# DCCInterfaceShieldNano.net
KiCad netlist of a schematic drawn in EAGLE
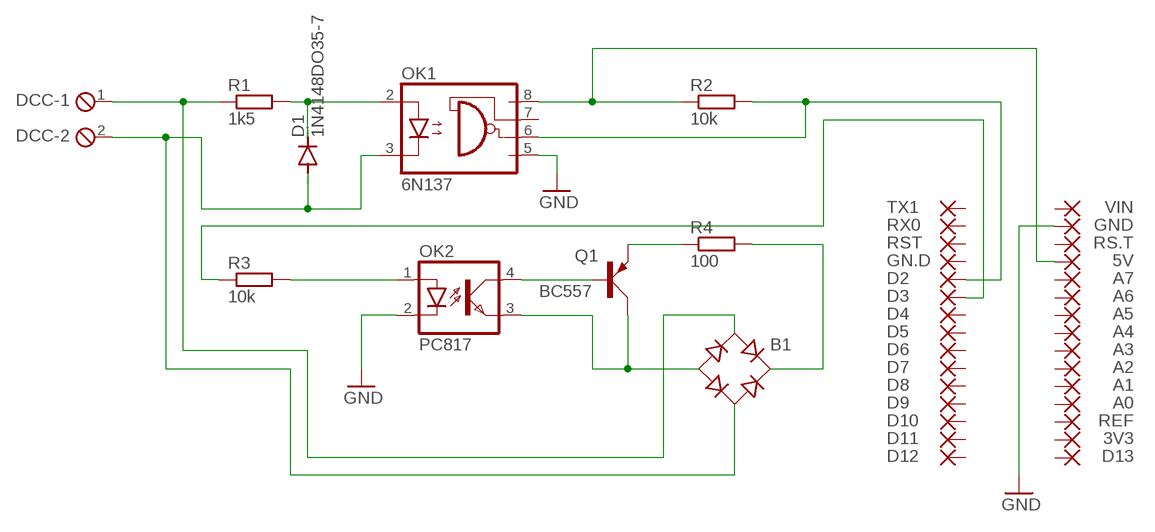
[diagram p0: schematic, sheet 1]

(export (version "E")
  (design (tool "Eeschema 10.0.6"))
  (components
    (comp (ref "3V3")
      (value "1,6/0,8")
      (footprint "eagle-import:1,6_0,8")
      (libsource (lib "eagle-import") (part "1,6/0,8"))
    )
    (comp (ref "5V")
      (value "1,6/0,8")
      (footprint "eagle-import:1,6_0,8")
      (libsource (lib "eagle-import") (part "1,6/0,8"))
    )
    (comp (ref "A0")
      (value "1,6/0,8")
      (footprint "eagle-import:1,6_0,8")
      (libsource (lib "eagle-import") (part "1,6/0,8"))
    )
    (comp (ref "A1")
      (value "1,6/0,8")
      (footprint "eagle-import:1,6_0,8")
      (libsource (lib "eagle-import") (part "1,6/0,8"))
    )
    (comp (ref "A2")
      (value "1,6/0,8")
      (footprint "eagle-import:1,6_0,8")
      (libsource (lib "eagle-import") (part "1,6/0,8"))
    )
    (comp (ref "A3")
      (value "1,6/0,8")
      (footprint "eagle-import:1,6_0,8")
      (libsource (lib "eagle-import") (part "1,6/0,8"))
    )
    (comp (ref "A4")
      (value "1,6/0,8")
      (footprint "eagle-import:1,6_0,8")
      (libsource (lib "eagle-import") (part "1,6/0,8"))
    )
    (comp (ref "A5")
      (value "1,6/0,8")
      (footprint "eagle-import:1,6_0,8")
      (libsource (lib "eagle-import") (part "1,6/0,8"))
    )
    (comp (ref "A6")
      (value "1,6/0,8")
      (footprint "eagle-import:1,6_0,8")
      (libsource (lib "eagle-import") (part "1,6/0,8"))
    )
    (comp (ref "A7")
      (value "1,6/0,8")
      (footprint "eagle-import:1,6_0,8")
      (libsource (lib "eagle-import") (part "1,6/0,8"))
    )
    (comp (ref "B1")
      (value "RB1A")
      (footprint "eagle-import:RB1A")
      (libsource (lib "eagle-import") (part "RB1A"))
    )
    (comp (ref "D1")
      (value "1N4148DO35-7")
      (footprint "eagle-import:DO35-7")
      (libsource (lib "eagle-import") (part "1N4148DO35-7"))
    )
    (comp (ref "D2")
      (value "1,6/0,8")
      (footprint "eagle-import:1,6_0,8")
      (libsource (lib "eagle-import") (part "1,6/0,8"))
    )
    (comp (ref "D3")
      (value "1,6/0,8")
      (footprint "eagle-import:1,6_0,8")
      (libsource (lib "eagle-import") (part "1,6/0,8"))
    )
    (comp (ref "D4")
      (value "1,6/0,8")
      (footprint "eagle-import:1,6_0,8")
      (libsource (lib "eagle-import") (part "1,6/0,8"))
    )
    (comp (ref "D5")
      (value "1,6/0,8")
      (footprint "eagle-import:1,6_0,8")
      (libsource (lib "eagle-import") (part "1,6/0,8"))
    )
    (comp (ref "D6")
      (value "1,6/0,8")
      (footprint "eagle-import:1,6_0,8")
      (libsource (lib "eagle-import") (part "1,6/0,8"))
    )
    (comp (ref "D7")
      (value "1,6/0,8")
      (footprint "eagle-import:1,6_0,8")
      (libsource (lib "eagle-import") (part "1,6/0,8"))
    )
    (comp (ref "D8")
      (value "1,6/0,8")
      (footprint "eagle-import:1,6_0,8")
      (libsource (lib "eagle-import") (part "1,6/0,8"))
    )
    (comp (ref "D9")
      (value "1,6/0,8")
      (footprint "eagle-import:1,6_0,8")
      (libsource (lib "eagle-import") (part "1,6/0,8"))
    )
    (comp (ref "D10")
      (value "1,6/0,8")
      (footprint "eagle-import:1,6_0,8")
      (libsource (lib "eagle-import") (part "1,6/0,8"))
    )
    (comp (ref "D11")
      (value "1,6/0,8")
      (footprint "eagle-import:1,6_0,8")
      (libsource (lib "eagle-import") (part "1,6/0,8"))
    )
    (comp (ref "D12")
      (value "1,6/0,8")
      (footprint "eagle-import:1,6_0,8")
      (libsource (lib "eagle-import") (part "1,6/0,8"))
    )
    (comp (ref "D13")
      (value "1,6/0,8")
      (footprint "eagle-import:1,6_0,8")
      (libsource (lib "eagle-import") (part "1,6/0,8"))
    )
    (comp (ref "DCC")
      (value "MPT2")
      (footprint "eagle-import:2POL254")
      (libsource (lib "eagle-import") (part "MPT2"))
    )
    (comp (ref "GN.D")
      (value "1,6/0,8")
      (footprint "eagle-import:1,6_0,8")
      (libsource (lib "eagle-import") (part "1,6/0,8"))
    )
    (comp (ref "GND")
      (value "1,6/0,8")
      (footprint "eagle-import:1,6_0,8")
      (libsource (lib "eagle-import") (part "1,6/0,8"))
    )
    (comp (ref "OK1")
      (value "6N137")
      (footprint "eagle-import:DIL08")
      (libsource (lib "eagle-import") (part "6N137"))
    )
    (comp (ref "OK2")
      (value "PC817")
      (footprint "eagle-import:DIL04")
      (fields (field (name "MPN") "PC817X4J000F"))
      (libsource (lib "eagle-import") (part "PC817"))
    )
    (comp (ref "Q1")
      (value "BC557")
      (footprint "eagle-import:SOT54A")
      (libsource (lib "eagle-import") (part "BC557"))
    )
    (comp (ref "R1")
      (value "1k5")
      (footprint "eagle-import:0204V")
      (libsource (lib "eagle-import") (part "R-EU_0204/2V"))
    )
    (comp (ref "R2")
      (value "10k")
      (footprint "eagle-import:0204V")
      (libsource (lib "eagle-import") (part "R-EU_0204/2V"))
    )
    (comp (ref "R3")
      (value "10k")
      (footprint "eagle-import:0204V")
      (libsource (lib "eagle-import") (part "R-EU_0204/2V"))
    )
    (comp (ref "R4")
      (value "100")
      (footprint "eagle-import:0204V")
      (libsource (lib "eagle-import") (part "R-EU_0204/2V"))
    )
    (comp (ref "REF")
      (value "1,6/0,8")
      (footprint "eagle-import:1,6_0,8")
      (libsource (lib "eagle-import") (part "1,6/0,8"))
    )
    (comp (ref "RS.T")
      (value "1,6/0,8")
      (footprint "eagle-import:1,6_0,8")
      (libsource (lib "eagle-import") (part "1,6/0,8"))
    )
    (comp (ref "RST")
      (value "1,6/0,8")
      (footprint "eagle-import:1,6_0,8")
      (libsource (lib "eagle-import") (part "1,6/0,8"))
    )
    (comp (ref "RX0")
      (value "1,6/0,8")
      (footprint "eagle-import:1,6_0,8")
      (libsource (lib "eagle-import") (part "1,6/0,8"))
    )
    (comp (ref "TX1")
      (value "1,6/0,8")
      (footprint "eagle-import:1,6_0,8")
      (libsource (lib "eagle-import") (part "1,6/0,8"))
    )
    (comp (ref "VIN")
      (value "1,6/0,8")
      (footprint "eagle-import:1,6_0,8")
      (libsource (lib "eagle-import") (part "1,6/0,8"))
    )
  )
  (nets
    (net (code "1") (name "GND") (class "Default")
      (node (ref "GND") (pin "1") (pinfunction "P_1") (pintype "passive"))
      (node (ref "OK1") (pin "5") (pinfunction "GND_5") (pintype "passive"))
      (node (ref "OK2") (pin "2") (pinfunction "C_2") (pintype "passive"))
    )
    (net (code "2") (name "Net-(5V-P)") (class "Default")
      (node (ref "5V") (pin "1") (pinfunction "P_1") (pintype "passive"))
      (node (ref "OK1") (pin "8") (pinfunction "VCC_8") (pintype "passive"))
      (node (ref "R2") (pin "1") (pinfunction "1_1") (pintype "passive"))
    )
    (net (code "3") (name "Net-(B1-Pad+)") (class "Default")
      (node (ref "B1") (pin "+") (pinfunction "+_+") (pintype "passive"))
      (node (ref "R4") (pin "2") (pinfunction "2_2") (pintype "passive"))
    )
    (net (code "4") (name "Net-(B1-PadAC1)") (class "Default")
      (node (ref "B1") (pin "AC1") (pinfunction "AC1_AC1") (pintype "passive"))
      (node (ref "DCC") (pin "1") (pinfunction "1_1") (pintype "passive"))
      (node (ref "R1") (pin "1") (pinfunction "1_1") (pintype "passive"))
    )
    (net (code "5") (name "Net-(D2-P)") (class "Default")
      (node (ref "D2") (pin "1") (pinfunction "P_1") (pintype "passive"))
      (node (ref "OK1") (pin "6") (pinfunction "VO_6") (pintype "passive"))
      (node (ref "R2") (pin "2") (pinfunction "2_2") (pintype "passive"))
    )
    (net (code "6") (name "Net-(D3-P)") (class "Default")
      (node (ref "D3") (pin "1") (pinfunction "P_1") (pintype "passive"))
      (node (ref "R3") (pin "1") (pinfunction "1_1") (pintype "passive"))
    )
    (net (code "7") (name "Net-(DCCB-1)") (class "Default")
      (node (ref "B1") (pin "AC2") (pinfunction "AC2_AC2") (pintype "passive"))
      (node (ref "D1") (pin "A") (pinfunction "A_A") (pintype "passive"))
      (node (ref "DCC") (pin "2") (pinfunction "1_2") (pintype "passive"))
      (node (ref "OK1") (pin "3") (pinfunction "C_3") (pintype "passive"))
    )
    (net (code "8") (name "Net-(OK1-A)") (class "Default")
      (node (ref "D1") (pin "C") (pinfunction "C_C") (pintype "passive"))
      (node (ref "OK1") (pin "2") (pinfunction "A_2") (pintype "passive"))
      (node (ref "R1") (pin "2") (pinfunction "2_2") (pintype "passive"))
    )
    (net (code "9") (name "Net-(OK2-A)") (class "Default")
      (node (ref "OK2") (pin "1") (pinfunction "A_1") (pintype "passive"))
      (node (ref "R3") (pin "2") (pinfunction "2_2") (pintype "passive"))
    )
    (net (code "10") (name "Net-(OK2-COL)") (class "Default")
      (node (ref "OK2") (pin "4") (pinfunction "COL_4") (pintype "passive"))
      (node (ref "Q1") (pin "B") (pinfunction "B_B") (pintype "passive"))
    )
    (net (code "11") (name "Net-(OK2-EMIT)") (class "Default")
      (node (ref "B1") (pin "-") (pinfunction "-_-") (pintype "passive"))
      (node (ref "OK2") (pin "3") (pinfunction "EMIT_3") (pintype "passive"))
      (node (ref "Q1") (pin "C") (pinfunction "C_C") (pintype "passive"))
    )
    (net (code "12") (name "Net-(Q1-PadE)") (class "Default")
      (node (ref "Q1") (pin "E") (pinfunction "E_E") (pintype "passive"))
      (node (ref "R4") (pin "1") (pinfunction "1_1") (pintype "passive"))
    )
    (net (code "13") (name "unconnected-(3V3-P-Pad1)") (class "Default")
      (node (ref "3V3") (pin "1") (pinfunction "P_1") (pintype "passive"))
    )
    (net (code "14") (name "unconnected-(A0-P-Pad1)") (class "Default")
      (node (ref "A0") (pin "1") (pinfunction "P_1") (pintype "passive"))
    )
    (net (code "15") (name "unconnected-(A1-P-Pad1)") (class "Default")
      (node (ref "A1") (pin "1") (pinfunction "P_1") (pintype "passive"))
    )
    (net (code "16") (name "unconnected-(A2-P-Pad1)") (class "Default")
      (node (ref "A2") (pin "1") (pinfunction "P_1") (pintype "passive"))
    )
    (net (code "17") (name "unconnected-(A3-P-Pad1)") (class "Default")
      (node (ref "A3") (pin "1") (pinfunction "P_1") (pintype "passive"))
    )
    (net (code "18") (name "unconnected-(A4-P-Pad1)") (class "Default")
      (node (ref "A4") (pin "1") (pinfunction "P_1") (pintype "passive"))
    )
    (net (code "19") (name "unconnected-(A5-P-Pad1)") (class "Default")
      (node (ref "A5") (pin "1") (pinfunction "P_1") (pintype "passive"))
    )
    (net (code "20") (name "unconnected-(A6-P-Pad1)") (class "Default")
      (node (ref "A6") (pin "1") (pinfunction "P_1") (pintype "passive"))
    )
    (net (code "21") (name "unconnected-(A7-P-Pad1)") (class "Default")
      (node (ref "A7") (pin "1") (pinfunction "P_1") (pintype "passive"))
    )
    (net (code "22") (name "unconnected-(D4-P-Pad1)") (class "Default")
      (node (ref "D4") (pin "1") (pinfunction "P_1") (pintype "passive"))
    )
    (net (code "23") (name "unconnected-(D5-P-Pad1)") (class "Default")
      (node (ref "D5") (pin "1") (pinfunction "P_1") (pintype "passive"))
    )
    (net (code "24") (name "unconnected-(D6-P-Pad1)") (class "Default")
      (node (ref "D6") (pin "1") (pinfunction "P_1") (pintype "passive"))
    )
    (net (code "25") (name "unconnected-(D7-P-Pad1)") (class "Default")
      (node (ref "D7") (pin "1") (pinfunction "P_1") (pintype "passive"))
    )
    (net (code "26") (name "unconnected-(D8-P-Pad1)") (class "Default")
      (node (ref "D8") (pin "1") (pinfunction "P_1") (pintype "passive"))
    )
    (net (code "27") (name "unconnected-(D9-P-Pad1)") (class "Default")
      (node (ref "D9") (pin "1") (pinfunction "P_1") (pintype "passive"))
    )
    (net (code "28") (name "unconnected-(D10-P-Pad1)") (class "Default")
      (node (ref "D10") (pin "1") (pinfunction "P_1") (pintype "passive"))
    )
    (net (code "29") (name "unconnected-(D11-P-Pad1)") (class "Default")
      (node (ref "D11") (pin "1") (pinfunction "P_1") (pintype "passive"))
    )
    (net (code "30") (name "unconnected-(D12-P-Pad1)") (class "Default")
      (node (ref "D12") (pin "1") (pinfunction "P_1") (pintype "passive"))
    )
    (net (code "31") (name "unconnected-(D13-P-Pad1)") (class "Default")
      (node (ref "D13") (pin "1") (pinfunction "P_1") (pintype "passive"))
    )
    (net (code "32") (name "unconnected-(GN.D-P-Pad1)") (class "Default")
      (node (ref "GN.D") (pin "1") (pinfunction "P_1") (pintype "passive"))
    )
    (net (code "33") (name "unconnected-(OK1-VE-Pad7)") (class "Default")
      (node (ref "OK1") (pin "7") (pinfunction "VE_7") (pintype "passive"))
    )
    (net (code "34") (name "unconnected-(REF-P-Pad1)") (class "Default")
      (node (ref "REF") (pin "1") (pinfunction "P_1") (pintype "passive"))
    )
    (net (code "35") (name "unconnected-(RS.T-P-Pad1)") (class "Default")
      (node (ref "RS.T") (pin "1") (pinfunction "P_1") (pintype "passive"))
    )
    (net (code "36") (name "unconnected-(RST-P-Pad1)") (class "Default")
      (node (ref "RST") (pin "1") (pinfunction "P_1") (pintype "passive"))
    )
    (net (code "37") (name "unconnected-(RX0-P-Pad1)") (class "Default")
      (node (ref "RX0") (pin "1") (pinfunction "P_1") (pintype "passive"))
    )
    (net (code "38") (name "unconnected-(TX1-P-Pad1)") (class "Default")
      (node (ref "TX1") (pin "1") (pinfunction "P_1") (pintype "passive"))
    )
    (net (code "39") (name "unconnected-(VIN-P-Pad1)") (class "Default")
      (node (ref "VIN") (pin "1") (pinfunction "P_1") (pintype "passive"))
    )
  )
)
